# 12V_Input_Protecion.net
KiCad netlist of a schematic drawn in Altium Designer
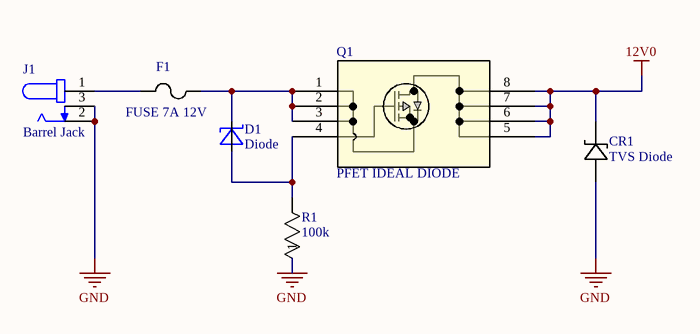
[diagram p0: 12V Input Protecion.SchDoc]

(export (version "E")
  (design (tool "Eeschema 10.0.6"))
  (components
    (comp (ref "CR1")
      (value "TVS Diode")
      (footprint "DO-214AASMB_J-BEND_LTF")
      (description "Description")
      (fields
        (field (name "MANUFACTURER_PART_NUMBER") "SMBJ15A")
        (field (name "COPYRIGHT") "Copyright (C) 2025 Ultra Librarian. All rights reserved.")
      )
      (libsource (lib "SMBJ15A") (part "SMBJ15A"))
    )
    (comp (ref "D1")
      (value "Diode")
      (footprint "SOD123")
      (description "Zener Diode 15V 6.1% 500mW SOD123 ¦ Diodes Inc BZT52C15-7-F")
      (fields (field (name "MF") "Diodes Inc.") (field (name "MP") "BZT52C15-7-F"))
      (libsource (lib "BZT52C15-7-F") (part "BZT52C15-7-F"))
    )
    (comp (ref "F1")
      (value "FUSE 7A 12V")
      (footprint "FUSE_2920L70012_LTF")
      (description "Description")
      (fields
        (field (name "MANUFACTURER_PART_NUMBER") "2920L700/12MR-A")
        (field (name "COPYRIGHT") "Copyright (C) 2025 Ultra Librarian. All rights reserved.")
      )
      (libsource (lib "2920L70012MR-A") (part "2920L70012MR-A"))
    )
    (comp (ref "J1")
      (value "Barrel Jack")
      (footprint "CUI_PJ-102AH")
      (description "2.0 x 6.5 mm, 5.0 A, Horizontal, Through Hole, Tapered Pins, Dc Power Jack Connector")
      (fields (field (name "MF") "Same Sky") (field (name "MP") "PJ-102AH"))
      (libsource (lib "PJ-102AH") (part "PJ-102AH"))
    )
    (comp (ref "Q1")
      (value "PFET IDEAL DIODE")
      (footprint "POWERPAK_SO-8_SINGLE_VIS")
      (description "P-CHANNEL 40-V (D-S) MOSFET")
      (fields
        (field (name "MANUFACTURER_PART_NUMBER") "SIR4409DP-T1-RE3")
        (field (name "COPYRIGHT") "Copyright (C) 2025 Ultra Librarian. All rights reserved.")
      )
      (libsource (lib "SIR4409DP-T1-RE3") (part "SIR4409DP-T1-RE3"))
    )
    (comp (ref "R1")
      (value "100k")
      (footprint "RC0805N_YAG")
      (description "Description")
      (fields
        (field (name "MANUFACTURER_PART_NUMBER") "RC0805FR-07100KL")
        (field (name "COPYRIGHT") "Copyright (C) 2025 Ultra Librarian. All rights reserved.")
      )
      (libsource (lib "RC0805FR-07100KL") (part "RC0805FR-07100KL"))
    )
  )
  (nets
    (net (code "1") (name "12V0") (class "Default")
      (node (ref "CR1") (pin "1") (pinfunction "1_1") (pintype "passive"))
      (node (ref "Q1") (pin "5") (pinfunction "D_5") (pintype "passive"))
      (node (ref "Q1") (pin "6") (pinfunction "D_6") (pintype "passive"))
      (node (ref "Q1") (pin "7") (pinfunction "D_7") (pintype "passive"))
      (node (ref "Q1") (pin "8") (pinfunction "D_8") (pintype "passive"))
    )
    (net (code "2") (name "GND") (class "Default")
      (node (ref "CR1") (pin "2") (pinfunction "2_2") (pintype "passive"))
      (node (ref "J1") (pin "2") (pinfunction "2_2") (pintype "passive"))
      (node (ref "J1") (pin "3") (pinfunction "3_3") (pintype "passive"))
      (node (ref "R1") (pin "1") (pinfunction "1_1") (pintype "passive"))
    )
    (net (code "3") (name "Net-(D1-PadC)") (class "Default")
      (node (ref "D1") (pin "C") (pinfunction "C_C") (pintype "passive"))
      (node (ref "F1") (pin "2") (pinfunction "2_2") (pintype "passive"))
      (node (ref "Q1") (pin "1") (pinfunction "S_1") (pintype "passive"))
      (node (ref "Q1") (pin "2") (pinfunction "S_2") (pintype "passive"))
      (node (ref "Q1") (pin "3") (pinfunction "S_3") (pintype "passive"))
    )
    (net (code "4") (name "Net-(F1-Pad1)") (class "Default")
      (node (ref "F1") (pin "1") (pinfunction "1_1") (pintype "passive"))
      (node (ref "J1") (pin "1") (pinfunction "1_1") (pintype "passive"))
    )
    (net (code "5") (name "Net-(Q1-G)") (class "Default")
      (node (ref "D1") (pin "A") (pinfunction "A_A") (pintype "passive"))
      (node (ref "Q1") (pin "4") (pinfunction "G_4") (pintype "passive"))
      (node (ref "R1") (pin "2") (pinfunction "2_2") (pintype "passive"))
    )
  )
)
